# Elaborato_2021-05-27.net
KiCad netlist of a schematic drawn in EasyEDA
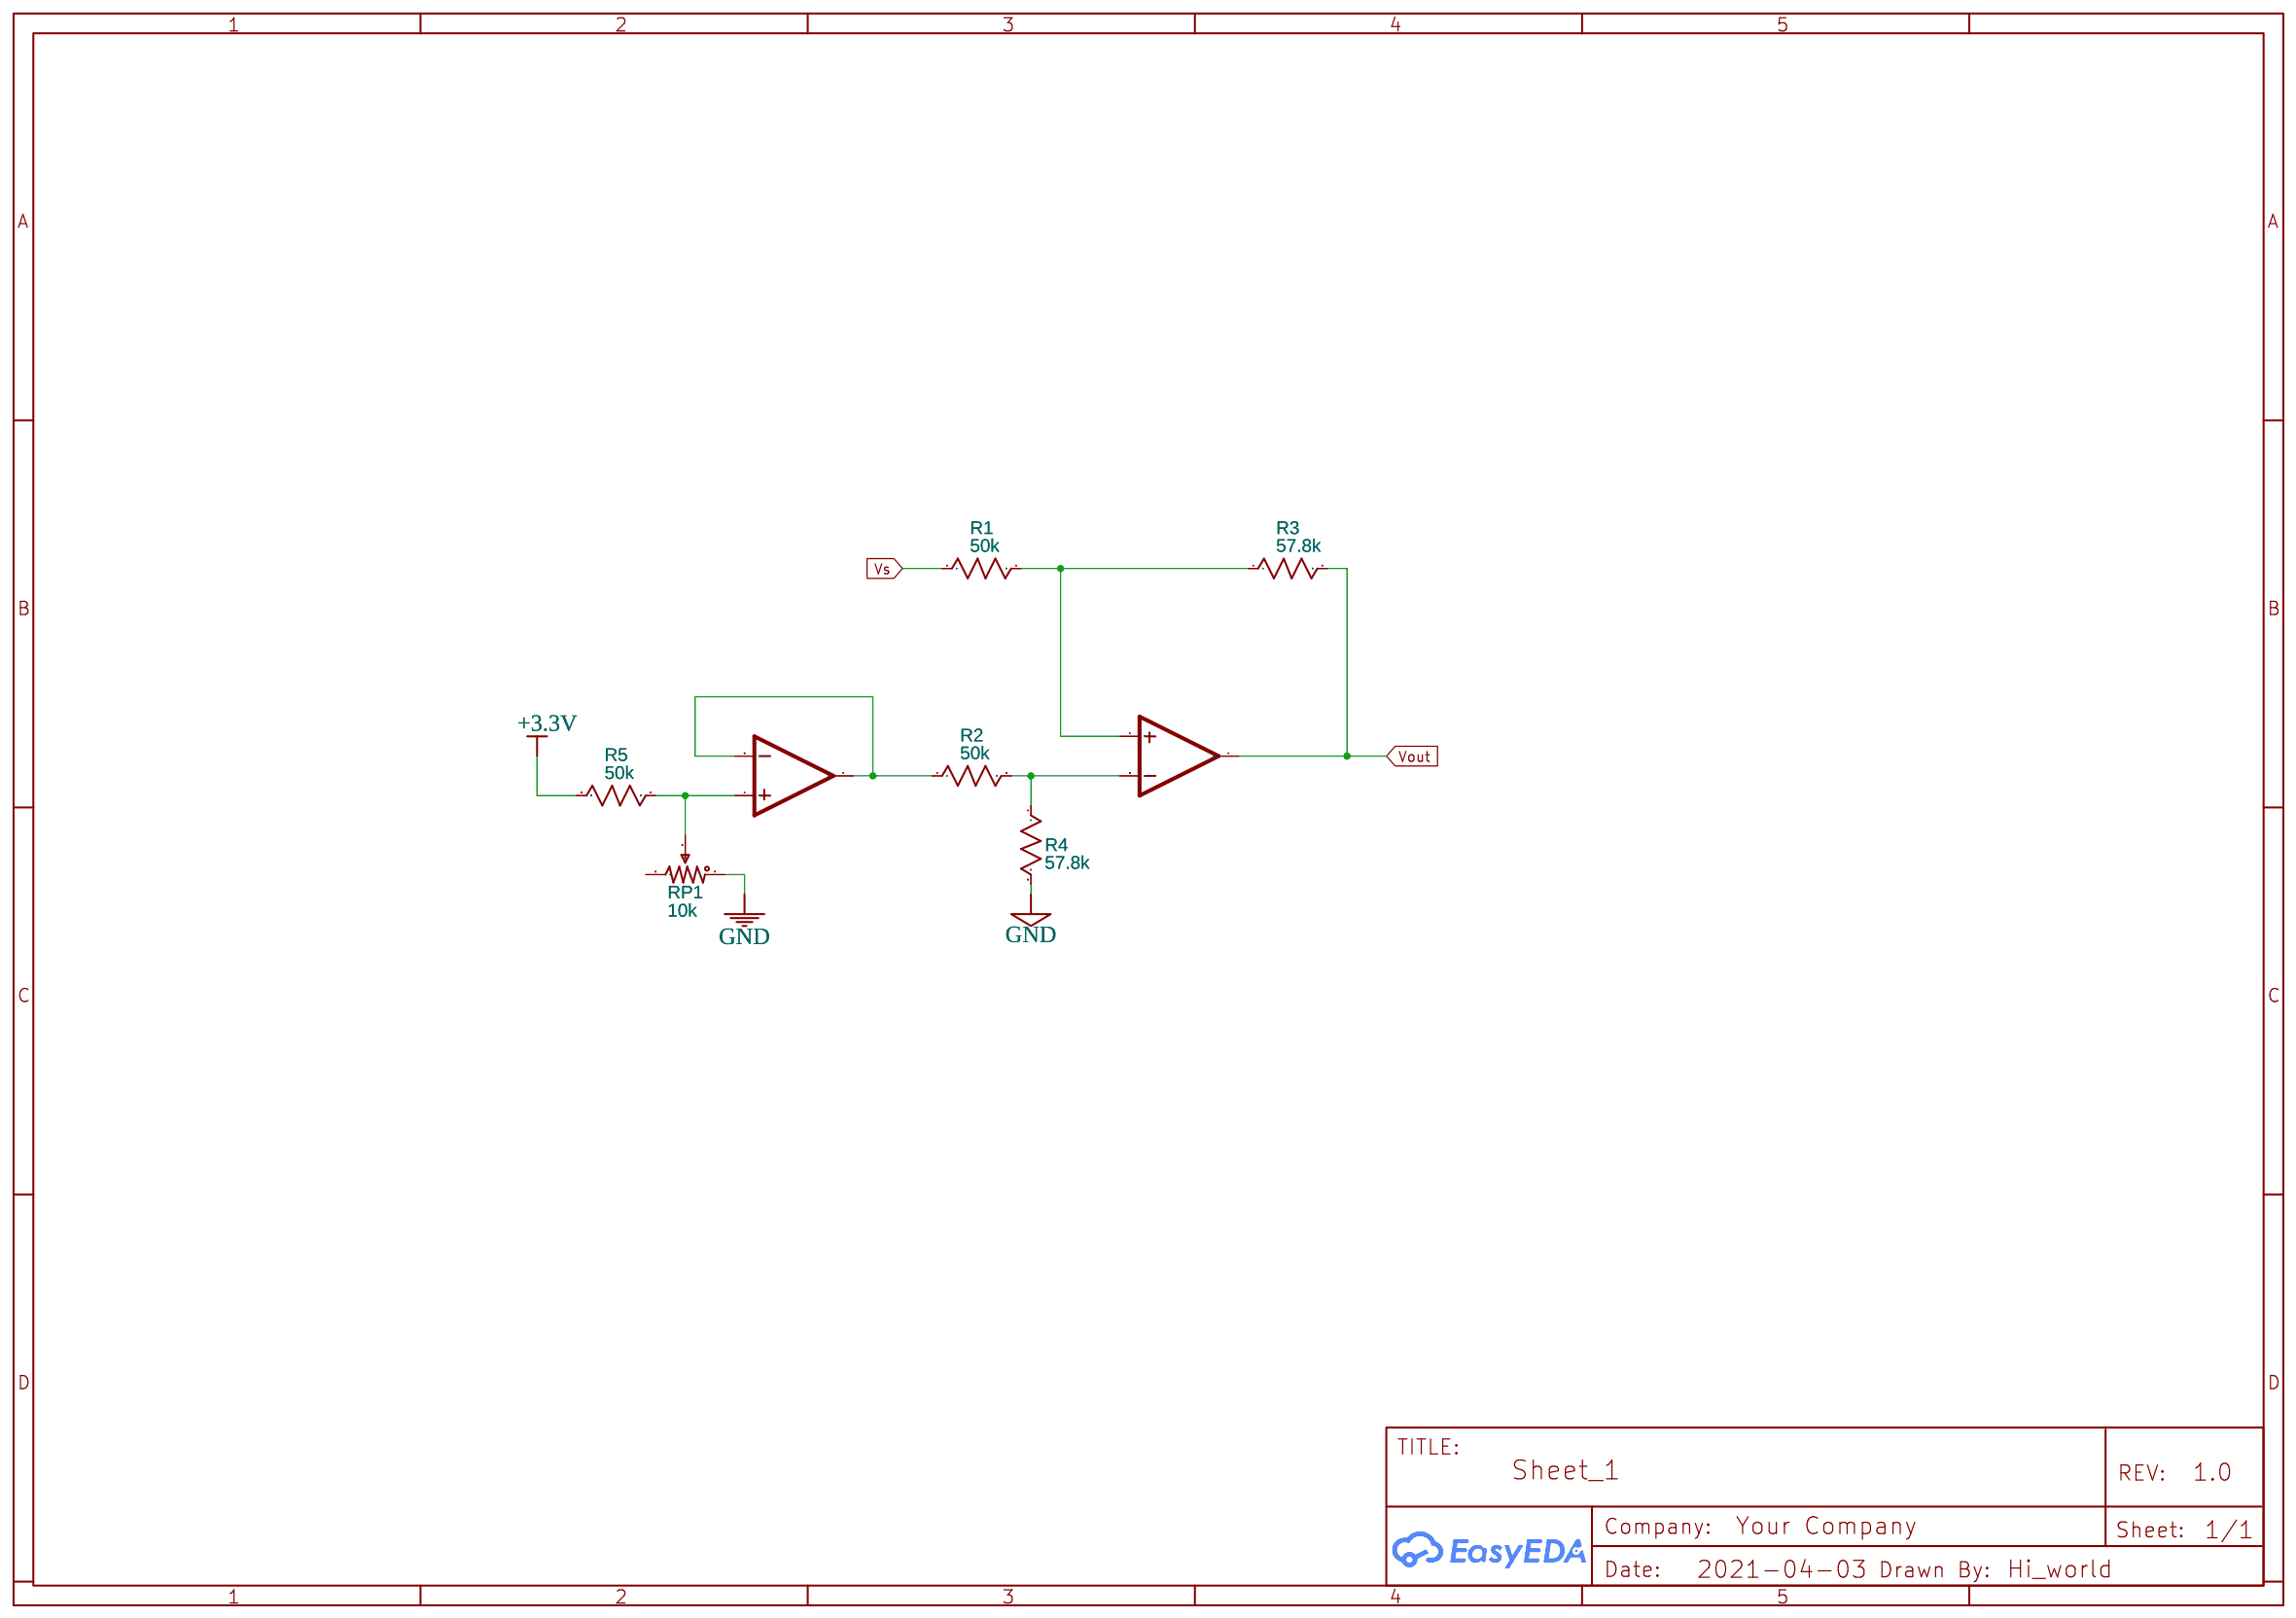
[diagram p0: Differenziale_condizionamento]
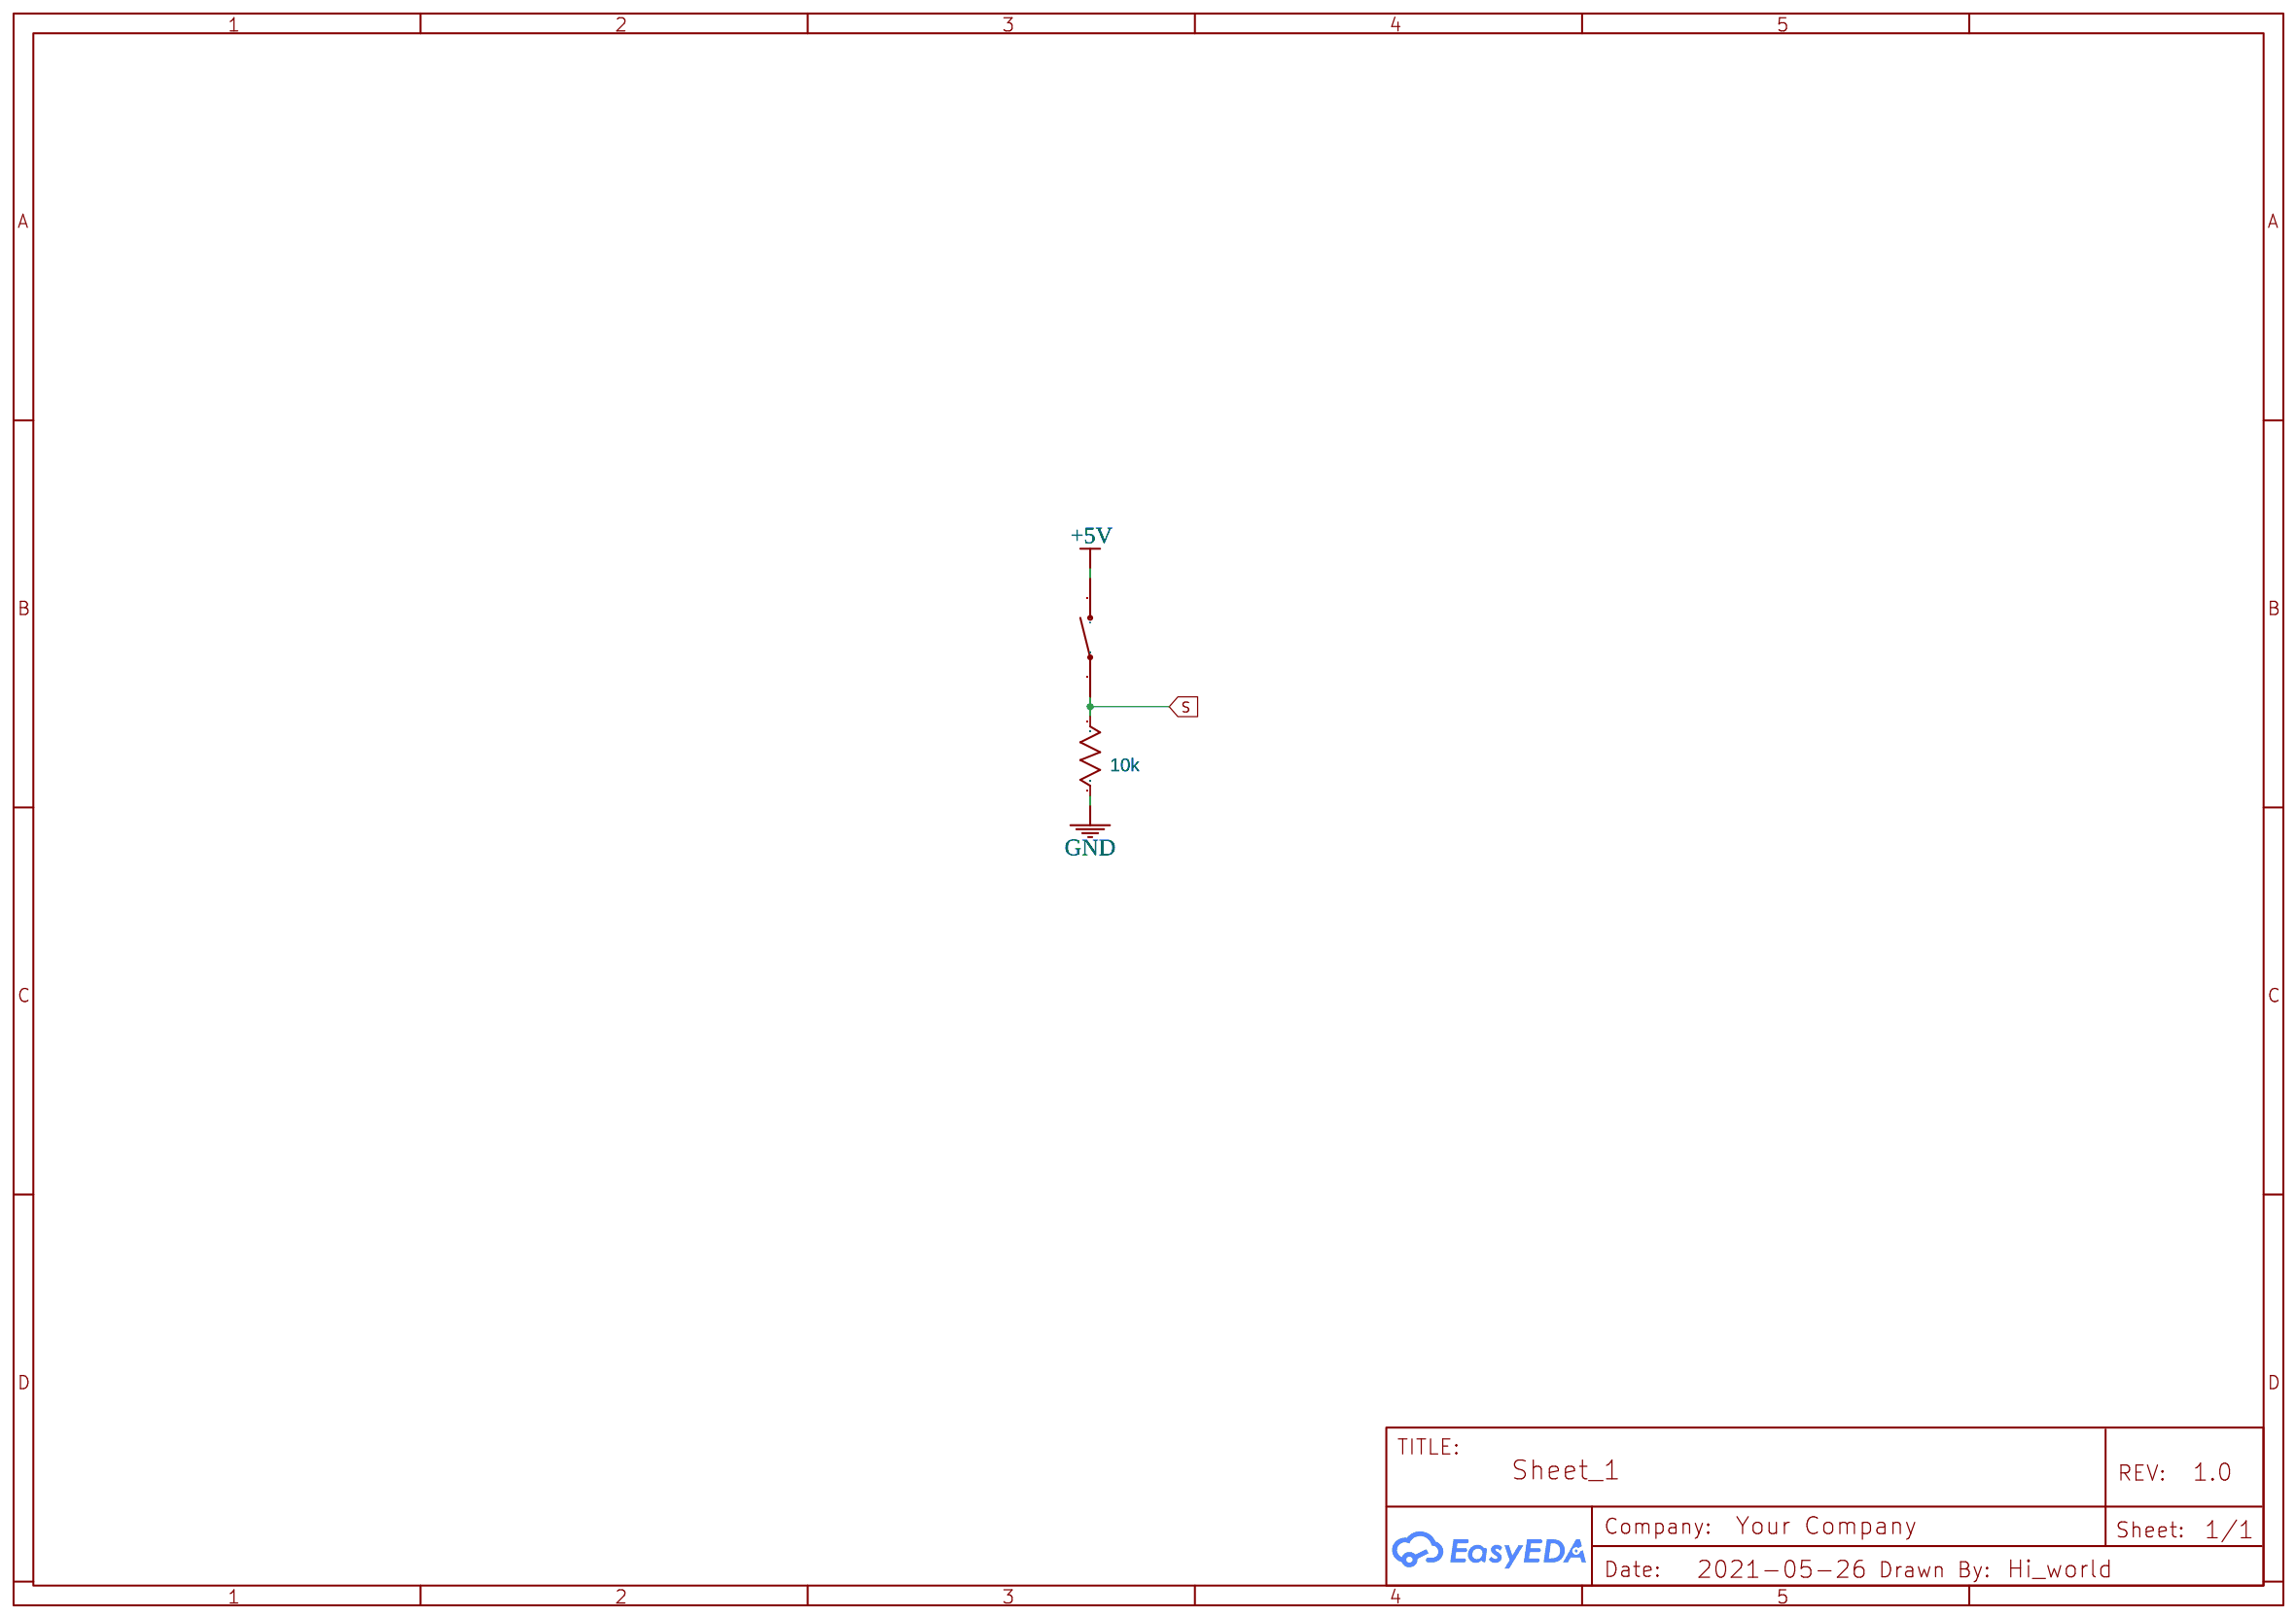
[diagram p1: Pull_down]
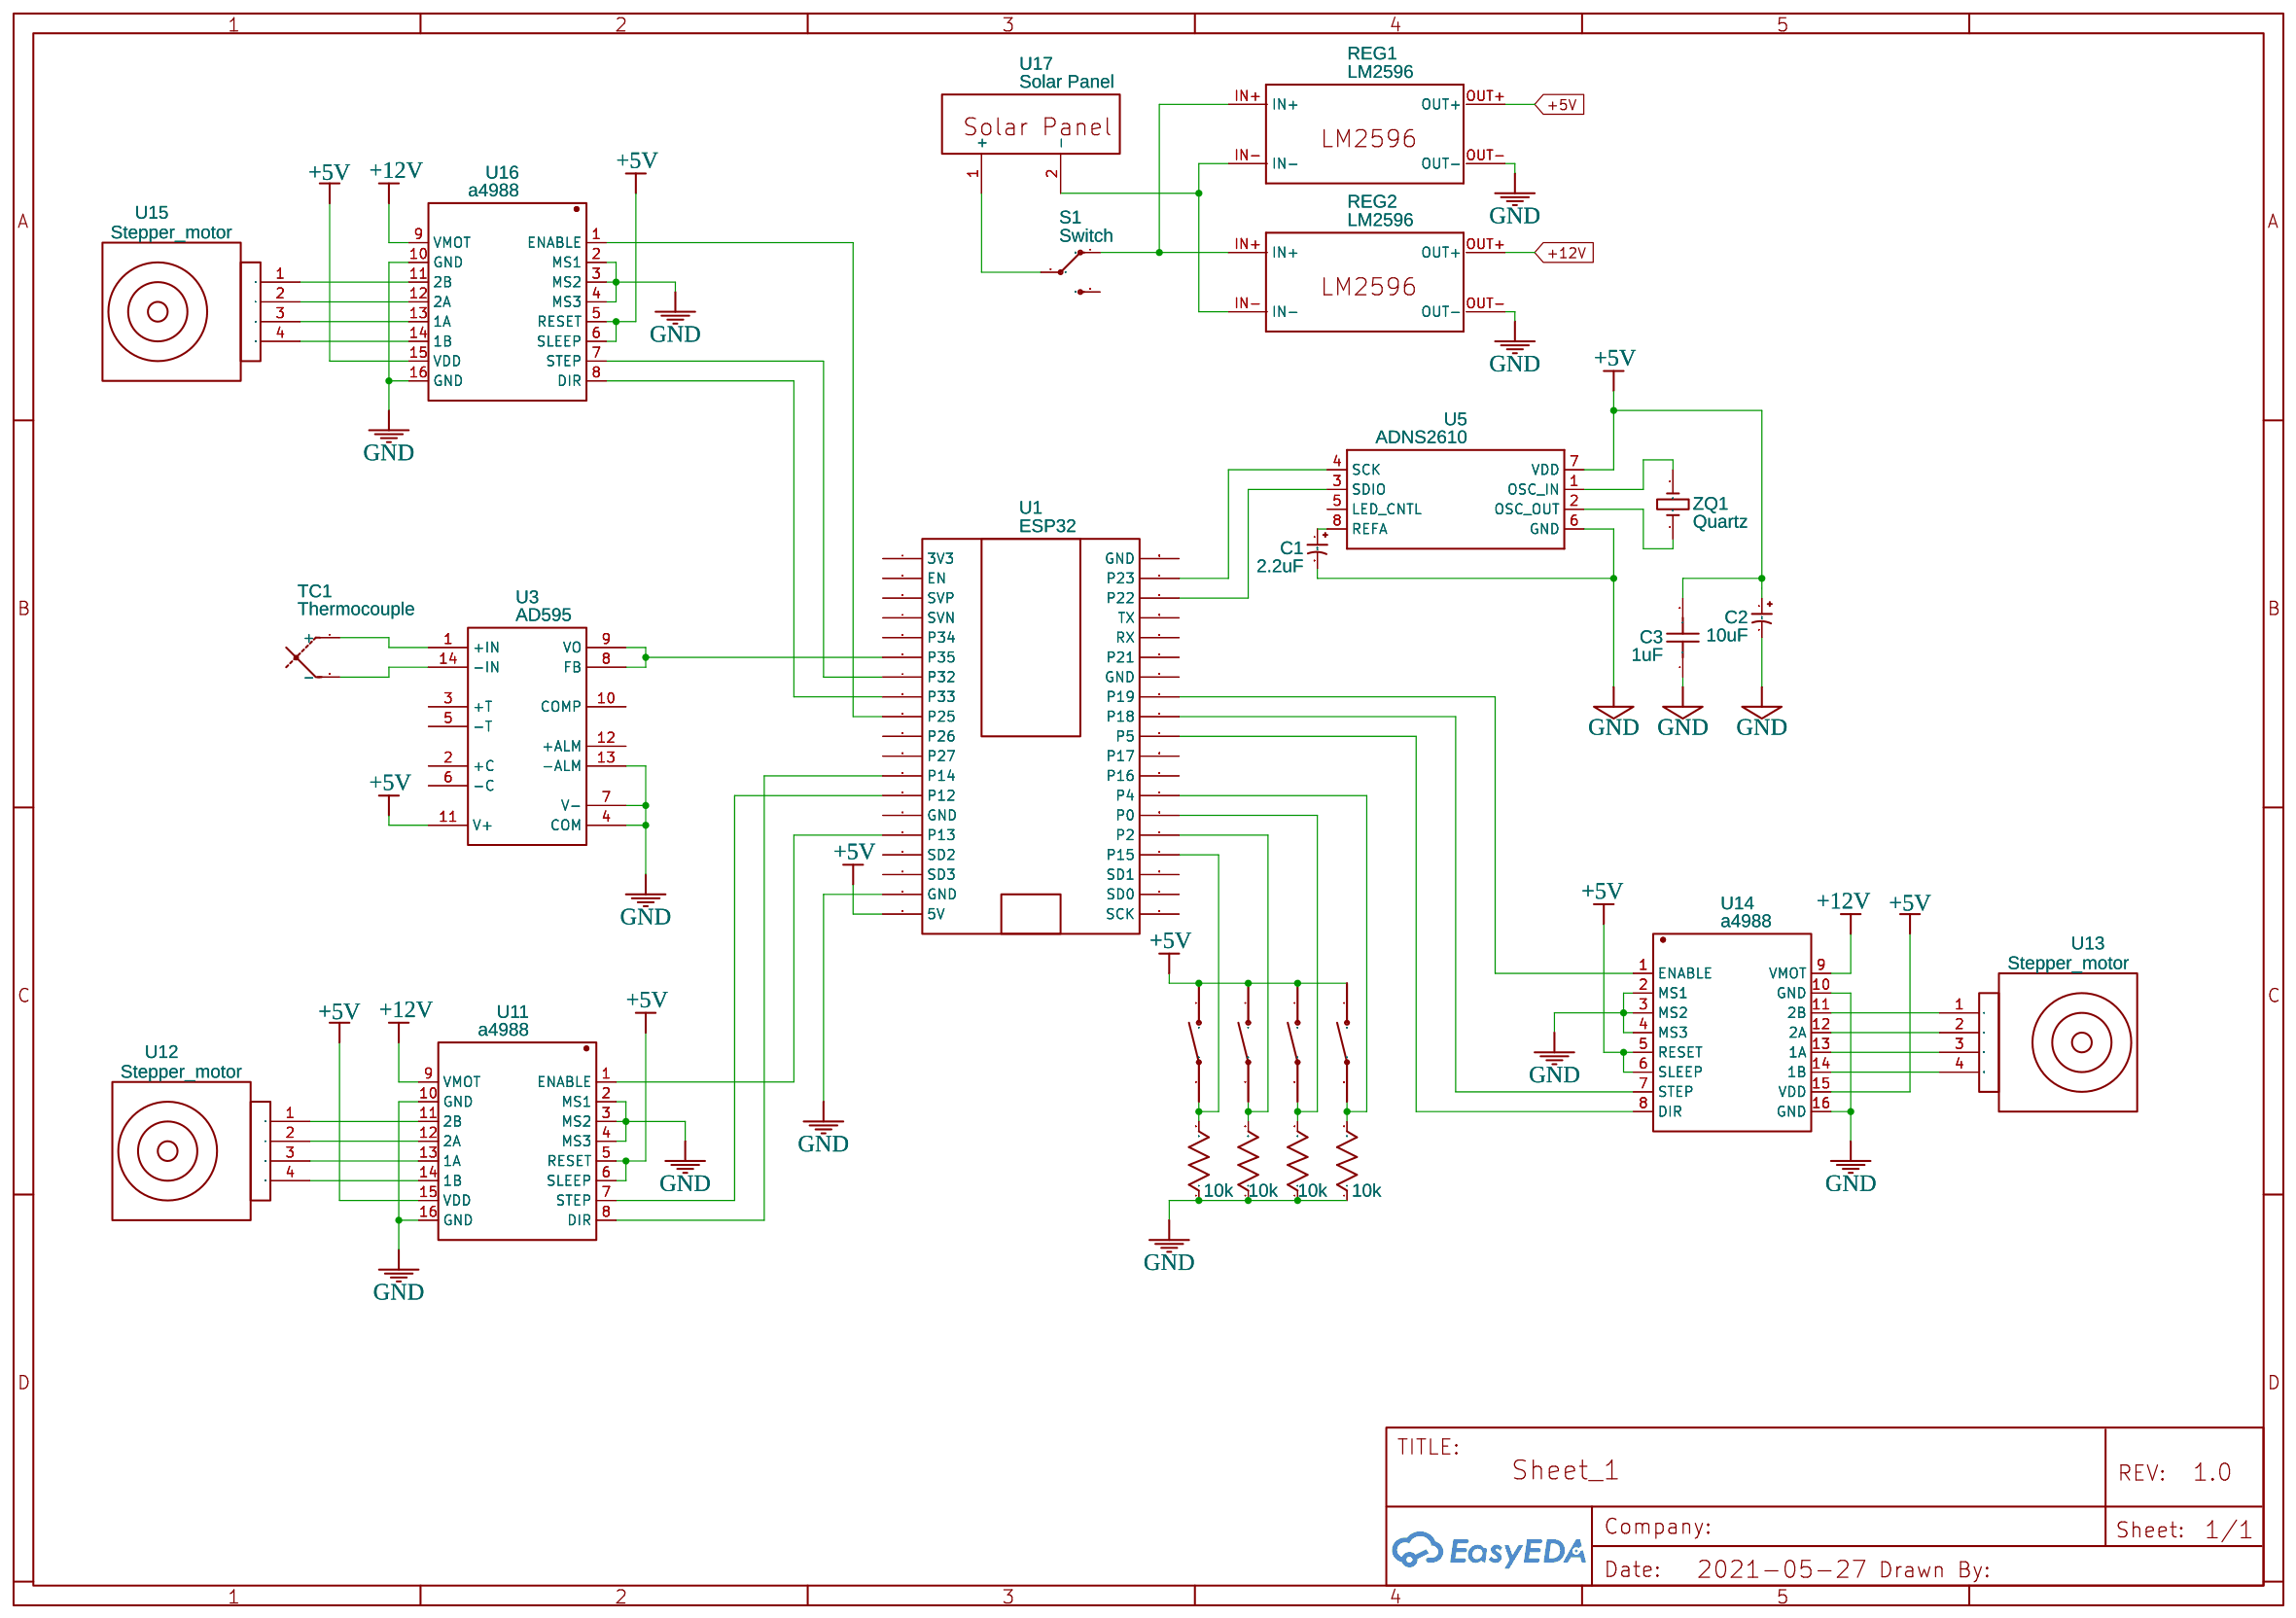
[diagram p2: Complete_schematic]

(export (version "E")
  (design (tool "Eeschema 10.0.6"))
  (components
    (comp (ref "R1") (value "50k") (libsource (lib "") (part "R_0603_US_1")))
    (comp (ref "R2") (value "50k") (libsource (lib "") (part "R_0603_US_1")))
    (comp (ref "R3") (value "57.8k") (libsource (lib "") (part "R_0603_US_1")))
    (comp (ref "R4") (value "57.8k") (libsource (lib "") (part "R_0603_US")))
    (comp (ref "R5") (value "50k") (libsource (lib "") (part "R_0603_US_2")))
    (comp (ref "RP1") (value "10k") (libsource (lib "") (part "R_3386P_US")))
    (comp (ref "U8")
      (value "Op amp")
      (fields
        (field (name "BOM_Manufacturer Part") "LMV321IDCKR")
        (field (name "BOM_Supplier Part") "310020013")
      )
      (libsource (lib "") (part "Op amp_1"))
    )
    (comp (ref "U9")
      (value "Op amp")
      (fields
        (field (name "BOM_Manufacturer Part") "LMV321IDCKR")
        (field (name "BOM_Supplier Part") "310020013")
      )
      (libsource (lib "") (part "Op amp"))
    )
    (comp (ref "R6") (value "10k") (libsource (lib "") (part "R_0603_US")))
    (comp (ref "U2")
      (value "Switch basic")
      (fields (field (name "BOM_Manufacturer Part") "Switch"))
      (libsource (lib "") (part "Switch basic"))
    )
    (comp (ref "C1") (value "2.2uF") (libsource (lib "") (part "Capacitor electrolitico 5mm_1")))
    (comp (ref "C2") (value "10uF") (libsource (lib "") (part "Capacitor electrolitico 5mm")))
    (comp (ref "C3") (value "1uF") (libsource (lib "") (part "Capacitor ceramico 5mm.PEQUEÑO")))
    (comp (ref "R7") (value "10k") (libsource (lib "") (part "R_0603_US")))
    (comp (ref "R8") (value "10k") (libsource (lib "") (part "R_0603_US")))
    (comp (ref "R9") (value "10k") (libsource (lib "") (part "R_0603_US")))
    (comp (ref "R10") (value "10k") (libsource (lib "") (part "R_0603_US")))
    (comp (ref "REG1") (value "LM2596") (libsource (lib "") (part "LM2596")))
    (comp (ref "REG2") (value "LM2596") (libsource (lib "") (part "LM2596")))
    (comp (ref "S1") (value "Switch") (libsource (lib "") (part "Switch")))
    (comp (ref "TC1") (value "Thermocouple") (libsource (lib "") (part "Thermocouple")))
    (comp (ref "U1")
      (value "ESP32")
      (fields (field (name "BOM_Manufacturer Part") "ESP-32S"))
      (libsource (lib "") (part "ESP32"))
    )
    (comp (ref "U3") (value "AD595") (libsource (lib "") (part "AD595ADZ")))
    (comp (ref "U4")
      (value "Switch basic")
      (fields (field (name "BOM_Manufacturer Part") "Switch"))
      (libsource (lib "") (part "Switch basic"))
    )
    (comp (ref "U5") (value "ADNS2610") (libsource (lib "") (part "ADNS2610")))
    (comp (ref "U6")
      (value "Switch basic")
      (fields (field (name "BOM_Manufacturer Part") "Switch"))
      (libsource (lib "") (part "Switch basic"))
    )
    (comp (ref "U7")
      (value "Switch basic")
      (fields (field (name "BOM_Manufacturer Part") "Switch"))
      (libsource (lib "") (part "Switch basic"))
    )
    (comp (ref "U10")
      (value "Switch basic")
      (fields (field (name "BOM_Manufacturer Part") "Switch"))
      (libsource (lib "") (part "Switch basic"))
    )
    (comp (ref "U11")
      (value "a4988")
      (fields
        (field (name "BOM_Manufacturer Part") "DRV8825PWPR")
        (field (name "BOM_Supplier Part") "C81582")
      )
      (libsource (lib "") (part "a4988"))
    )
    (comp (ref "U12")
      (value "Stepper_motor")
      (fields (field (name "BOM_Manufacturer Part") "NEMA 23 Stepper Motor"))
      (libsource (lib "") (part "Stepper_motor"))
    )
    (comp (ref "U13")
      (value "Stepper_motor")
      (fields (field (name "BOM_Manufacturer Part") "NEMA 23 Stepper Motor"))
      (libsource (lib "") (part "Stepper_motor_1"))
    )
    (comp (ref "U14")
      (value "a4988")
      (fields
        (field (name "BOM_Manufacturer Part") "DRV8825PWPR")
        (field (name "BOM_Supplier Part") "C81582")
      )
      (libsource (lib "") (part "a4988_1"))
    )
    (comp (ref "U15")
      (value "Stepper_motor")
      (fields (field (name "BOM_Manufacturer Part") "NEMA 23 Stepper Motor"))
      (libsource (lib "") (part "Stepper_motor"))
    )
    (comp (ref "U16")
      (value "a4988")
      (fields
        (field (name "BOM_Manufacturer Part") "DRV8825PWPR")
        (field (name "BOM_Supplier Part") "C81582")
      )
      (libsource (lib "") (part "a4988"))
    )
    (comp (ref "U17") (value "Solar Panel") (libsource (lib "") (part "Solar Panel")))
    (comp (ref "ZQ1")
      (value "Quartz")
      (fields (field (name "BOM_Manufacturer Part") "New SchematicLib"))
      (libsource (lib "") (part "Quartz"))
    )
  )
  (nets
    (net (code "1") (name "+3.3V") (class "Default")
      (node (ref "R5") (pin "2") (pinfunction "2_2") (pintype "unspecified"))
    )
    (net (code "2") (name "+5V") (class "Default")
      (node (ref "C2") (pin "1") (pinfunction "1_1") (pintype "unspecified"))
      (node (ref "C3") (pin "2") (pinfunction "2_2") (pintype "unspecified"))
      (node (ref "REG1") (pin "OUT+") (pinfunction "OUT+_OUT+") (pintype "bidirectional"))
      (node (ref "U1") (pin "19") (pinfunction "5V_19") (pintype "unspecified"))
      (node (ref "U10") (pin "1") (pinfunction "1_1") (pintype "unspecified"))
      (node (ref "U11") (pin "15") (pinfunction "VDD_15") (pintype "unspecified"))
      (node (ref "U11") (pin "5") (pinfunction "RESET_5") (pintype "unspecified"))
      (node (ref "U11") (pin "6") (pinfunction "SLEEP_6") (pintype "unspecified"))
      (node (ref "U14") (pin "15") (pinfunction "VDD_15") (pintype "unspecified"))
      (node (ref "U14") (pin "5") (pinfunction "RESET_5") (pintype "unspecified"))
      (node (ref "U14") (pin "6") (pinfunction "SLEEP_6") (pintype "unspecified"))
      (node (ref "U16") (pin "15") (pinfunction "VDD_15") (pintype "unspecified"))
      (node (ref "U16") (pin "5") (pinfunction "RESET_5") (pintype "unspecified"))
      (node (ref "U16") (pin "6") (pinfunction "SLEEP_6") (pintype "unspecified"))
      (node (ref "U2") (pin "1") (pinfunction "1_1") (pintype "unspecified"))
      (node (ref "U3") (pin "11") (pinfunction "V+_11") (pintype "passive"))
      (node (ref "U4") (pin "1") (pinfunction "1_1") (pintype "unspecified"))
      (node (ref "U5") (pin "7") (pinfunction "VDD_7") (pintype "unspecified"))
      (node (ref "U6") (pin "1") (pinfunction "1_1") (pintype "unspecified"))
      (node (ref "U7") (pin "1") (pinfunction "1_1") (pintype "unspecified"))
    )
    (net (code "3") (name "+12V") (class "Default")
      (node (ref "REG2") (pin "OUT+") (pinfunction "OUT+_OUT+") (pintype "bidirectional"))
      (node (ref "U11") (pin "9") (pinfunction "VMOT_9") (pintype "unspecified"))
      (node (ref "U14") (pin "9") (pinfunction "VMOT_9") (pintype "unspecified"))
      (node (ref "U16") (pin "9") (pinfunction "VMOT_9") (pintype "unspecified"))
    )
    (net (code "4") (name "GND") (class "Default")
      (node (ref "C1") (pin "2") (pinfunction "2_2") (pintype "unspecified"))
      (node (ref "C2") (pin "2") (pinfunction "2_2") (pintype "unspecified"))
      (node (ref "C3") (pin "1") (pinfunction "1_1") (pintype "unspecified"))
      (node (ref "R10") (pin "1") (pinfunction "1_1") (pintype "unspecified"))
      (node (ref "R4") (pin "2") (pinfunction "2_2") (pintype "unspecified"))
      (node (ref "R6") (pin "1") (pinfunction "1_1") (pintype "unspecified"))
      (node (ref "R7") (pin "1") (pinfunction "1_1") (pintype "unspecified"))
      (node (ref "R8") (pin "1") (pinfunction "1_1") (pintype "unspecified"))
      (node (ref "R9") (pin "1") (pinfunction "1_1") (pintype "unspecified"))
      (node (ref "REG1") (pin "OUT-") (pinfunction "OUT-_OUT-") (pintype "bidirectional"))
      (node (ref "REG2") (pin "OUT-") (pinfunction "OUT-_OUT-") (pintype "bidirectional"))
      (node (ref "RP1") (pin "1") (pinfunction "1_1") (pintype "unspecified"))
      (node (ref "U1") (pin "18") (pinfunction "GND_18") (pintype "unspecified"))
      (node (ref "U11") (pin "10") (pinfunction "GND_10") (pintype "unspecified"))
      (node (ref "U11") (pin "16") (pinfunction "GND_16") (pintype "unspecified"))
      (node (ref "U11") (pin "2") (pinfunction "MS1_2") (pintype "unspecified"))
      (node (ref "U11") (pin "3") (pinfunction "MS2_3") (pintype "unspecified"))
      (node (ref "U11") (pin "4") (pinfunction "MS3_4") (pintype "unspecified"))
      (node (ref "U14") (pin "10") (pinfunction "GND_10") (pintype "unspecified"))
      (node (ref "U14") (pin "16") (pinfunction "GND_16") (pintype "unspecified"))
      (node (ref "U14") (pin "2") (pinfunction "MS1_2") (pintype "unspecified"))
      (node (ref "U14") (pin "3") (pinfunction "MS2_3") (pintype "unspecified"))
      (node (ref "U14") (pin "4") (pinfunction "MS3_4") (pintype "unspecified"))
      (node (ref "U16") (pin "10") (pinfunction "GND_10") (pintype "unspecified"))
      (node (ref "U16") (pin "16") (pinfunction "GND_16") (pintype "unspecified"))
      (node (ref "U16") (pin "2") (pinfunction "MS1_2") (pintype "unspecified"))
      (node (ref "U16") (pin "3") (pinfunction "MS2_3") (pintype "unspecified"))
      (node (ref "U16") (pin "4") (pinfunction "MS3_4") (pintype "unspecified"))
      (node (ref "U3") (pin "13") (pinfunction "-ALM_13") (pintype "unspecified"))
      (node (ref "U3") (pin "4") (pinfunction "COM_4") (pintype "passive"))
      (node (ref "U3") (pin "7") (pinfunction "V-_7") (pintype "passive"))
      (node (ref "U5") (pin "6") (pinfunction "GND_6") (pintype "unspecified"))
    )
    (net (code "5") (name "Net-(S1-O)") (class "Default")
      (node (ref "REG1") (pin "IN+") (pinfunction "IN+_IN+") (pintype "bidirectional"))
      (node (ref "REG2") (pin "IN+") (pinfunction "IN+_IN+") (pintype "bidirectional"))
      (node (ref "S1") (pin "1") (pinfunction "O_1") (pintype "unspecified"))
    )
    (net (code "6") (name "Net-(S1-P)") (class "Default")
      (node (ref "S1") (pin "2") (pinfunction "P_2") (pintype "unspecified"))
      (node (ref "U17") (pin "1") (pinfunction "+_1") (pintype "unspecified"))
    )
    (net (code "7") (name "Net-(TC1-+)") (class "Default")
      (node (ref "TC1") (pin "1") (pinfunction "+_1") (pintype "unspecified"))
      (node (ref "U3") (pin "1") (pinfunction "+IN_1") (pintype "unspecified"))
    )
    (net (code "8") (name "Net-(TC1--)") (class "Default")
      (node (ref "TC1") (pin "2") (pinfunction "-_2") (pintype "unspecified"))
      (node (ref "U3") (pin "14") (pinfunction "-IN_14") (pintype "unspecified"))
    )
    (net (code "9") (name "Net-(U1-P0)") (class "Default")
      (node (ref "R9") (pin "2") (pinfunction "2_2") (pintype "unspecified"))
      (node (ref "U1") (pin "25") (pinfunction "P0_25") (pintype "unspecified"))
      (node (ref "U7") (pin "2") (pinfunction "2_2") (pintype "unspecified"))
    )
    (net (code "10") (name "Net-(U1-P2)") (class "Default")
      (node (ref "R8") (pin "2") (pinfunction "2_2") (pintype "unspecified"))
      (node (ref "U1") (pin "24") (pinfunction "P2_24") (pintype "unspecified"))
      (node (ref "U6") (pin "2") (pinfunction "2_2") (pintype "unspecified"))
    )
    (net (code "11") (name "Net-(U1-P4)") (class "Default")
      (node (ref "R10") (pin "2") (pinfunction "2_2") (pintype "unspecified"))
      (node (ref "U1") (pin "26") (pinfunction "P4_26") (pintype "unspecified"))
      (node (ref "U10") (pin "2") (pinfunction "2_2") (pintype "unspecified"))
    )
    (net (code "12") (name "Net-(U1-P5)") (class "Default")
      (node (ref "U1") (pin "29") (pinfunction "P5_29") (pintype "unspecified"))
      (node (ref "U14") (pin "8") (pinfunction "DIR_8") (pintype "unspecified"))
    )
    (net (code "13") (name "Net-(U1-P12)") (class "Default")
      (node (ref "U1") (pin "13") (pinfunction "P12_13") (pintype "unspecified"))
      (node (ref "U11") (pin "7") (pinfunction "STEP_7") (pintype "unspecified"))
    )
    (net (code "14") (name "Net-(U1-P13)") (class "Default")
      (node (ref "U1") (pin "15") (pinfunction "P13_15") (pintype "unspecified"))
      (node (ref "U11") (pin "1") (pinfunction "ENABLE_1") (pintype "unspecified"))
    )
    (net (code "15") (name "Net-(U1-P14)") (class "Default")
      (node (ref "U1") (pin "12") (pinfunction "P14_12") (pintype "unspecified"))
      (node (ref "U11") (pin "8") (pinfunction "DIR_8") (pintype "unspecified"))
    )
    (net (code "16") (name "Net-(U1-P15)") (class "Default")
      (node (ref "R7") (pin "2") (pinfunction "2_2") (pintype "unspecified"))
      (node (ref "U1") (pin "23") (pinfunction "P15_23") (pintype "unspecified"))
      (node (ref "U4") (pin "2") (pinfunction "2_2") (pintype "unspecified"))
    )
    (net (code "17") (name "Net-(U1-P18)") (class "Default")
      (node (ref "U1") (pin "30") (pinfunction "P18_30") (pintype "unspecified"))
      (node (ref "U14") (pin "7") (pinfunction "STEP_7") (pintype "unspecified"))
    )
    (net (code "18") (name "Net-(U1-P19)") (class "Default")
      (node (ref "U1") (pin "31") (pinfunction "P19_31") (pintype "unspecified"))
      (node (ref "U14") (pin "1") (pinfunction "ENABLE_1") (pintype "unspecified"))
    )
    (net (code "19") (name "Net-(U1-P22)") (class "Default")
      (node (ref "U1") (pin "36") (pinfunction "P22_36") (pintype "unspecified"))
      (node (ref "U5") (pin "3") (pinfunction "SDIO_3") (pintype "unspecified"))
    )
    (net (code "20") (name "Net-(U1-P23)") (class "Default")
      (node (ref "U1") (pin "37") (pinfunction "P23_37") (pintype "unspecified"))
      (node (ref "U5") (pin "4") (pinfunction "SCK_4") (pintype "unspecified"))
    )
    (net (code "21") (name "Net-(U1-P25)") (class "Default")
      (node (ref "U1") (pin "9") (pinfunction "P25_9") (pintype "unspecified"))
      (node (ref "U16") (pin "1") (pinfunction "ENABLE_1") (pintype "unspecified"))
    )
    (net (code "22") (name "Net-(U1-P32)") (class "Default")
      (node (ref "U1") (pin "7") (pinfunction "P32_7") (pintype "unspecified"))
      (node (ref "U16") (pin "7") (pinfunction "STEP_7") (pintype "unspecified"))
    )
    (net (code "23") (name "Net-(U1-P33)") (class "Default")
      (node (ref "U1") (pin "8") (pinfunction "P33_8") (pintype "unspecified"))
      (node (ref "U16") (pin "8") (pinfunction "DIR_8") (pintype "unspecified"))
    )
    (net (code "24") (name "Net-(U1-P35)") (class "Default")
      (node (ref "U1") (pin "6") (pinfunction "P35_6") (pintype "unspecified"))
      (node (ref "U3") (pin "8") (pinfunction "FB_8") (pintype "unspecified"))
      (node (ref "U3") (pin "9") (pinfunction "VO_9") (pintype "output"))
    )
    (net (code "25") (name "Net-(U5-OSC_IN)") (class "Default")
      (node (ref "U5") (pin "1") (pinfunction "OSC_IN_1") (pintype "unspecified"))
      (node (ref "ZQ1") (pin "2") (pinfunction "2_2") (pintype "unspecified"))
    )
    (net (code "26") (name "Net-(U5-OSC_OUT)") (class "Default")
      (node (ref "U5") (pin "2") (pinfunction "OSC_OUT_2") (pintype "unspecified"))
      (node (ref "ZQ1") (pin "1") (pinfunction "1_1") (pintype "unspecified"))
    )
    (net (code "27") (name "Net-(U5-REFA)") (class "Default")
      (node (ref "C1") (pin "1") (pinfunction "1_1") (pintype "unspecified"))
      (node (ref "U5") (pin "8") (pinfunction "REFA_8") (pintype "unspecified"))
    )
    (net (code "28") (name "Net-(U8-IN+)") (class "Default")
      (node (ref "R5") (pin "1") (pinfunction "1_1") (pintype "unspecified"))
      (node (ref "RP1") (pin "2") (pinfunction "2_2") (pintype "unspecified"))
      (node (ref "U8") (pin "1") (pinfunction "IN+_1") (pintype "input"))
    )
    (net (code "29") (name "Net-(U8-IN-)") (class "Default")
      (node (ref "R2") (pin "1") (pinfunction "1_1") (pintype "unspecified"))
      (node (ref "U8") (pin "3") (pinfunction "IN-_3") (pintype "input"))
      (node (ref "U8") (pin "4") (pinfunction "OUT_4") (pintype "output"))
    )
    (net (code "30") (name "Net-(U9-IN+)") (class "Default")
      (node (ref "R1") (pin "2") (pinfunction "2_2") (pintype "unspecified"))
      (node (ref "R3") (pin "1") (pinfunction "1_1") (pintype "unspecified"))
      (node (ref "U9") (pin "1") (pinfunction "IN+_1") (pintype "input"))
    )
    (net (code "31") (name "Net-(U9-IN-)") (class "Default")
      (node (ref "R2") (pin "2") (pinfunction "2_2") (pintype "unspecified"))
      (node (ref "R4") (pin "1") (pinfunction "1_1") (pintype "unspecified"))
      (node (ref "U9") (pin "3") (pinfunction "IN-_3") (pintype "input"))
    )
    (net (code "32") (name "Net-(U11-1A)") (class "Default")
      (node (ref "U11") (pin "13") (pinfunction "1A_13") (pintype "unspecified"))
      (node (ref "U12") (pin "3") (pinfunction "B+_3") (pintype "unspecified"))
    )
    (net (code "33") (name "Net-(U11-1B)") (class "Default")
      (node (ref "U11") (pin "14") (pinfunction "1B_14") (pintype "unspecified"))
      (node (ref "U12") (pin "4") (pinfunction "B-_4") (pintype "unspecified"))
    )
    (net (code "34") (name "Net-(U11-2A)") (class "Default")
      (node (ref "U11") (pin "12") (pinfunction "2A_12") (pintype "unspecified"))
      (node (ref "U12") (pin "2") (pinfunction "A-_2") (pintype "unspecified"))
    )
    (net (code "35") (name "Net-(U11-2B)") (class "Default")
      (node (ref "U11") (pin "11") (pinfunction "2B_11") (pintype "unspecified"))
      (node (ref "U12") (pin "1") (pinfunction "A+_1") (pintype "unspecified"))
    )
    (net (code "36") (name "Net-(U13-A+)") (class "Default")
      (node (ref "U13") (pin "1") (pinfunction "A+_1") (pintype "unspecified"))
      (node (ref "U14") (pin "11") (pinfunction "2B_11") (pintype "unspecified"))
    )
    (net (code "37") (name "Net-(U13-A-)") (class "Default")
      (node (ref "U13") (pin "2") (pinfunction "A-_2") (pintype "unspecified"))
      (node (ref "U14") (pin "12") (pinfunction "2A_12") (pintype "unspecified"))
    )
    (net (code "38") (name "Net-(U13-B+)") (class "Default")
      (node (ref "U13") (pin "3") (pinfunction "B+_3") (pintype "unspecified"))
      (node (ref "U14") (pin "13") (pinfunction "1A_13") (pintype "unspecified"))
    )
    (net (code "39") (name "Net-(U13-B-)") (class "Default")
      (node (ref "U13") (pin "4") (pinfunction "B-_4") (pintype "unspecified"))
      (node (ref "U14") (pin "14") (pinfunction "1B_14") (pintype "unspecified"))
    )
    (net (code "40") (name "Net-(U15-A+)") (class "Default")
      (node (ref "U15") (pin "1") (pinfunction "A+_1") (pintype "unspecified"))
      (node (ref "U16") (pin "11") (pinfunction "2B_11") (pintype "unspecified"))
    )
    (net (code "41") (name "Net-(U15-A-)") (class "Default")
      (node (ref "U15") (pin "2") (pinfunction "A-_2") (pintype "unspecified"))
      (node (ref "U16") (pin "12") (pinfunction "2A_12") (pintype "unspecified"))
    )
    (net (code "42") (name "Net-(U15-B+)") (class "Default")
      (node (ref "U15") (pin "3") (pinfunction "B+_3") (pintype "unspecified"))
      (node (ref "U16") (pin "13") (pinfunction "1A_13") (pintype "unspecified"))
    )
    (net (code "43") (name "Net-(U15-B-)") (class "Default")
      (node (ref "U15") (pin "4") (pinfunction "B-_4") (pintype "unspecified"))
      (node (ref "U16") (pin "14") (pinfunction "1B_14") (pintype "unspecified"))
    )
    (net (code "44") (name "Net-(U17--)") (class "Default")
      (node (ref "REG1") (pin "IN-") (pinfunction "IN-_IN-") (pintype "bidirectional"))
      (node (ref "REG2") (pin "IN-") (pinfunction "IN-_IN-") (pintype "bidirectional"))
      (node (ref "U17") (pin "2") (pinfunction "-_2") (pintype "unspecified"))
    )
    (net (code "45") (name "S") (class "Default")
      (node (ref "R6") (pin "2") (pinfunction "2_2") (pintype "unspecified"))
      (node (ref "U2") (pin "2") (pinfunction "2_2") (pintype "unspecified"))
    )
    (net (code "46") (name "Vout") (class "Default")
      (node (ref "R3") (pin "2") (pinfunction "2_2") (pintype "unspecified"))
      (node (ref "U9") (pin "4") (pinfunction "OUT_4") (pintype "output"))
    )
    (net (code "47") (name "Vs") (class "Default")
      (node (ref "R1") (pin "1") (pinfunction "1_1") (pintype "unspecified"))
    )
    (net (code "48") (name "unconnected-(RP1-Pad3)") (class "Default")
      (node (ref "RP1") (pin "3") (pinfunction "3_3") (pintype "unspecified"))
    )
    (net (code "49") (name "unconnected-(S1-S-Pad3)") (class "Default")
      (node (ref "S1") (pin "3") (pinfunction "S_3") (pintype "unspecified"))
    )
    (net (code "50") (name "unconnected-(U1-3V3-Pad1)") (class "Default")
      (node (ref "U1") (pin "1") (pinfunction "3V3_1") (pintype "unspecified"))
    )
    (net (code "51") (name "unconnected-(U1-EN-Pad2)") (class "Default")
      (node (ref "U1") (pin "2") (pinfunction "EN_2") (pintype "unspecified"))
    )
    (net (code "52") (name "unconnected-(U1-GND-Pad14)") (class "Default")
      (node (ref "U1") (pin "14") (pinfunction "GND_14") (pintype "unspecified"))
    )
    (net (code "53") (name "unconnected-(U1-GND-Pad32)") (class "Default")
      (node (ref "U1") (pin "32") (pinfunction "GND_32") (pintype "unspecified"))
    )
    (net (code "54") (name "unconnected-(U1-GND-Pad38)") (class "Default")
      (node (ref "U1") (pin "38") (pinfunction "GND_38") (pintype "unspecified"))
    )
    (net (code "55") (name "unconnected-(U1-P16-Pad27)") (class "Default")
      (node (ref "U1") (pin "27") (pinfunction "P16_27") (pintype "unspecified"))
    )
    (net (code "56") (name "unconnected-(U1-P17-Pad28)") (class "Default")
      (node (ref "U1") (pin "28") (pinfunction "P17_28") (pintype "unspecified"))
    )
    (net (code "57") (name "unconnected-(U1-P21-Pad33)") (class "Default")
      (node (ref "U1") (pin "33") (pinfunction "P21_33") (pintype "unspecified"))
    )
    (net (code "58") (name "unconnected-(U1-P26-Pad10)") (class "Default")
      (node (ref "U1") (pin "10") (pinfunction "P26_10") (pintype "unspecified"))
    )
    (net (code "59") (name "unconnected-(U1-P27-Pad11)") (class "Default")
      (node (ref "U1") (pin "11") (pinfunction "P27_11") (pintype "unspecified"))
    )
    (net (code "60") (name "unconnected-(U1-P34-Pad5)") (class "Default")
      (node (ref "U1") (pin "5") (pinfunction "P34_5") (pintype "unspecified"))
    )
    (net (code "61") (name "unconnected-(U1-RX-Pad34)") (class "Default")
      (node (ref "U1") (pin "34") (pinfunction "RX_34") (pintype "unspecified"))
    )
    (net (code "62") (name "unconnected-(U1-SCK-Pad20)") (class "Default")
      (node (ref "U1") (pin "20") (pinfunction "SCK_20") (pintype "unspecified"))
    )
    (net (code "63") (name "unconnected-(U1-SD0-Pad21)") (class "Default")
      (node (ref "U1") (pin "21") (pinfunction "SD0_21") (pintype "unspecified"))
    )
    (net (code "64") (name "unconnected-(U1-SD1-Pad22)") (class "Default")
      (node (ref "U1") (pin "22") (pinfunction "SD1_22") (pintype "unspecified"))
    )
    (net (code "65") (name "unconnected-(U1-SD2-Pad16)") (class "Default")
      (node (ref "U1") (pin "16") (pinfunction "SD2_16") (pintype "unspecified"))
    )
    (net (code "66") (name "unconnected-(U1-SD3-Pad17)") (class "Default")
      (node (ref "U1") (pin "17") (pinfunction "SD3_17") (pintype "unspecified"))
    )
    (net (code "67") (name "unconnected-(U1-SVN-Pad4)") (class "Default")
      (node (ref "U1") (pin "4") (pinfunction "SVN_4") (pintype "unspecified"))
    )
    (net (code "68") (name "unconnected-(U1-SVP-Pad3)") (class "Default")
      (node (ref "U1") (pin "3") (pinfunction "SVP_3") (pintype "unspecified"))
    )
    (net (code "69") (name "unconnected-(U1-TX-Pad35)") (class "Default")
      (node (ref "U1") (pin "35") (pinfunction "TX_35") (pintype "unspecified"))
    )
    (net (code "70") (name "unconnected-(U3-+ALM-Pad12)") (class "Default")
      (node (ref "U3") (pin "12") (pinfunction "+ALM_12") (pintype "unspecified"))
    )
    (net (code "71") (name "unconnected-(U3-+C-Pad2)") (class "Default")
      (node (ref "U3") (pin "2") (pinfunction "+C_2") (pintype "unspecified"))
    )
    (net (code "72") (name "unconnected-(U3-+T-Pad3)") (class "Default")
      (node (ref "U3") (pin "3") (pinfunction "+T_3") (pintype "unspecified"))
    )
    (net (code "73") (name "unconnected-(U3--C-Pad6)") (class "Default")
      (node (ref "U3") (pin "6") (pinfunction "-C_6") (pintype "unspecified"))
    )
    (net (code "74") (name "unconnected-(U3--T-Pad5)") (class "Default")
      (node (ref "U3") (pin "5") (pinfunction "-T_5") (pintype "unspecified"))
    )
    (net (code "75") (name "unconnected-(U3-COMP-Pad10)") (class "Default")
      (node (ref "U3") (pin "10") (pinfunction "COMP_10") (pintype "output"))
    )
    (net (code "76") (name "unconnected-(U5-LED_CNTL-Pad5)") (class "Default")
      (node (ref "U5") (pin "5") (pinfunction "LED_CNTL_5") (pintype "unspecified"))
    )
  )
)
